# CaRe_Schematic_SMD_KRITIKARE.net
KiCad netlist of a schematic drawn in Altium Designer
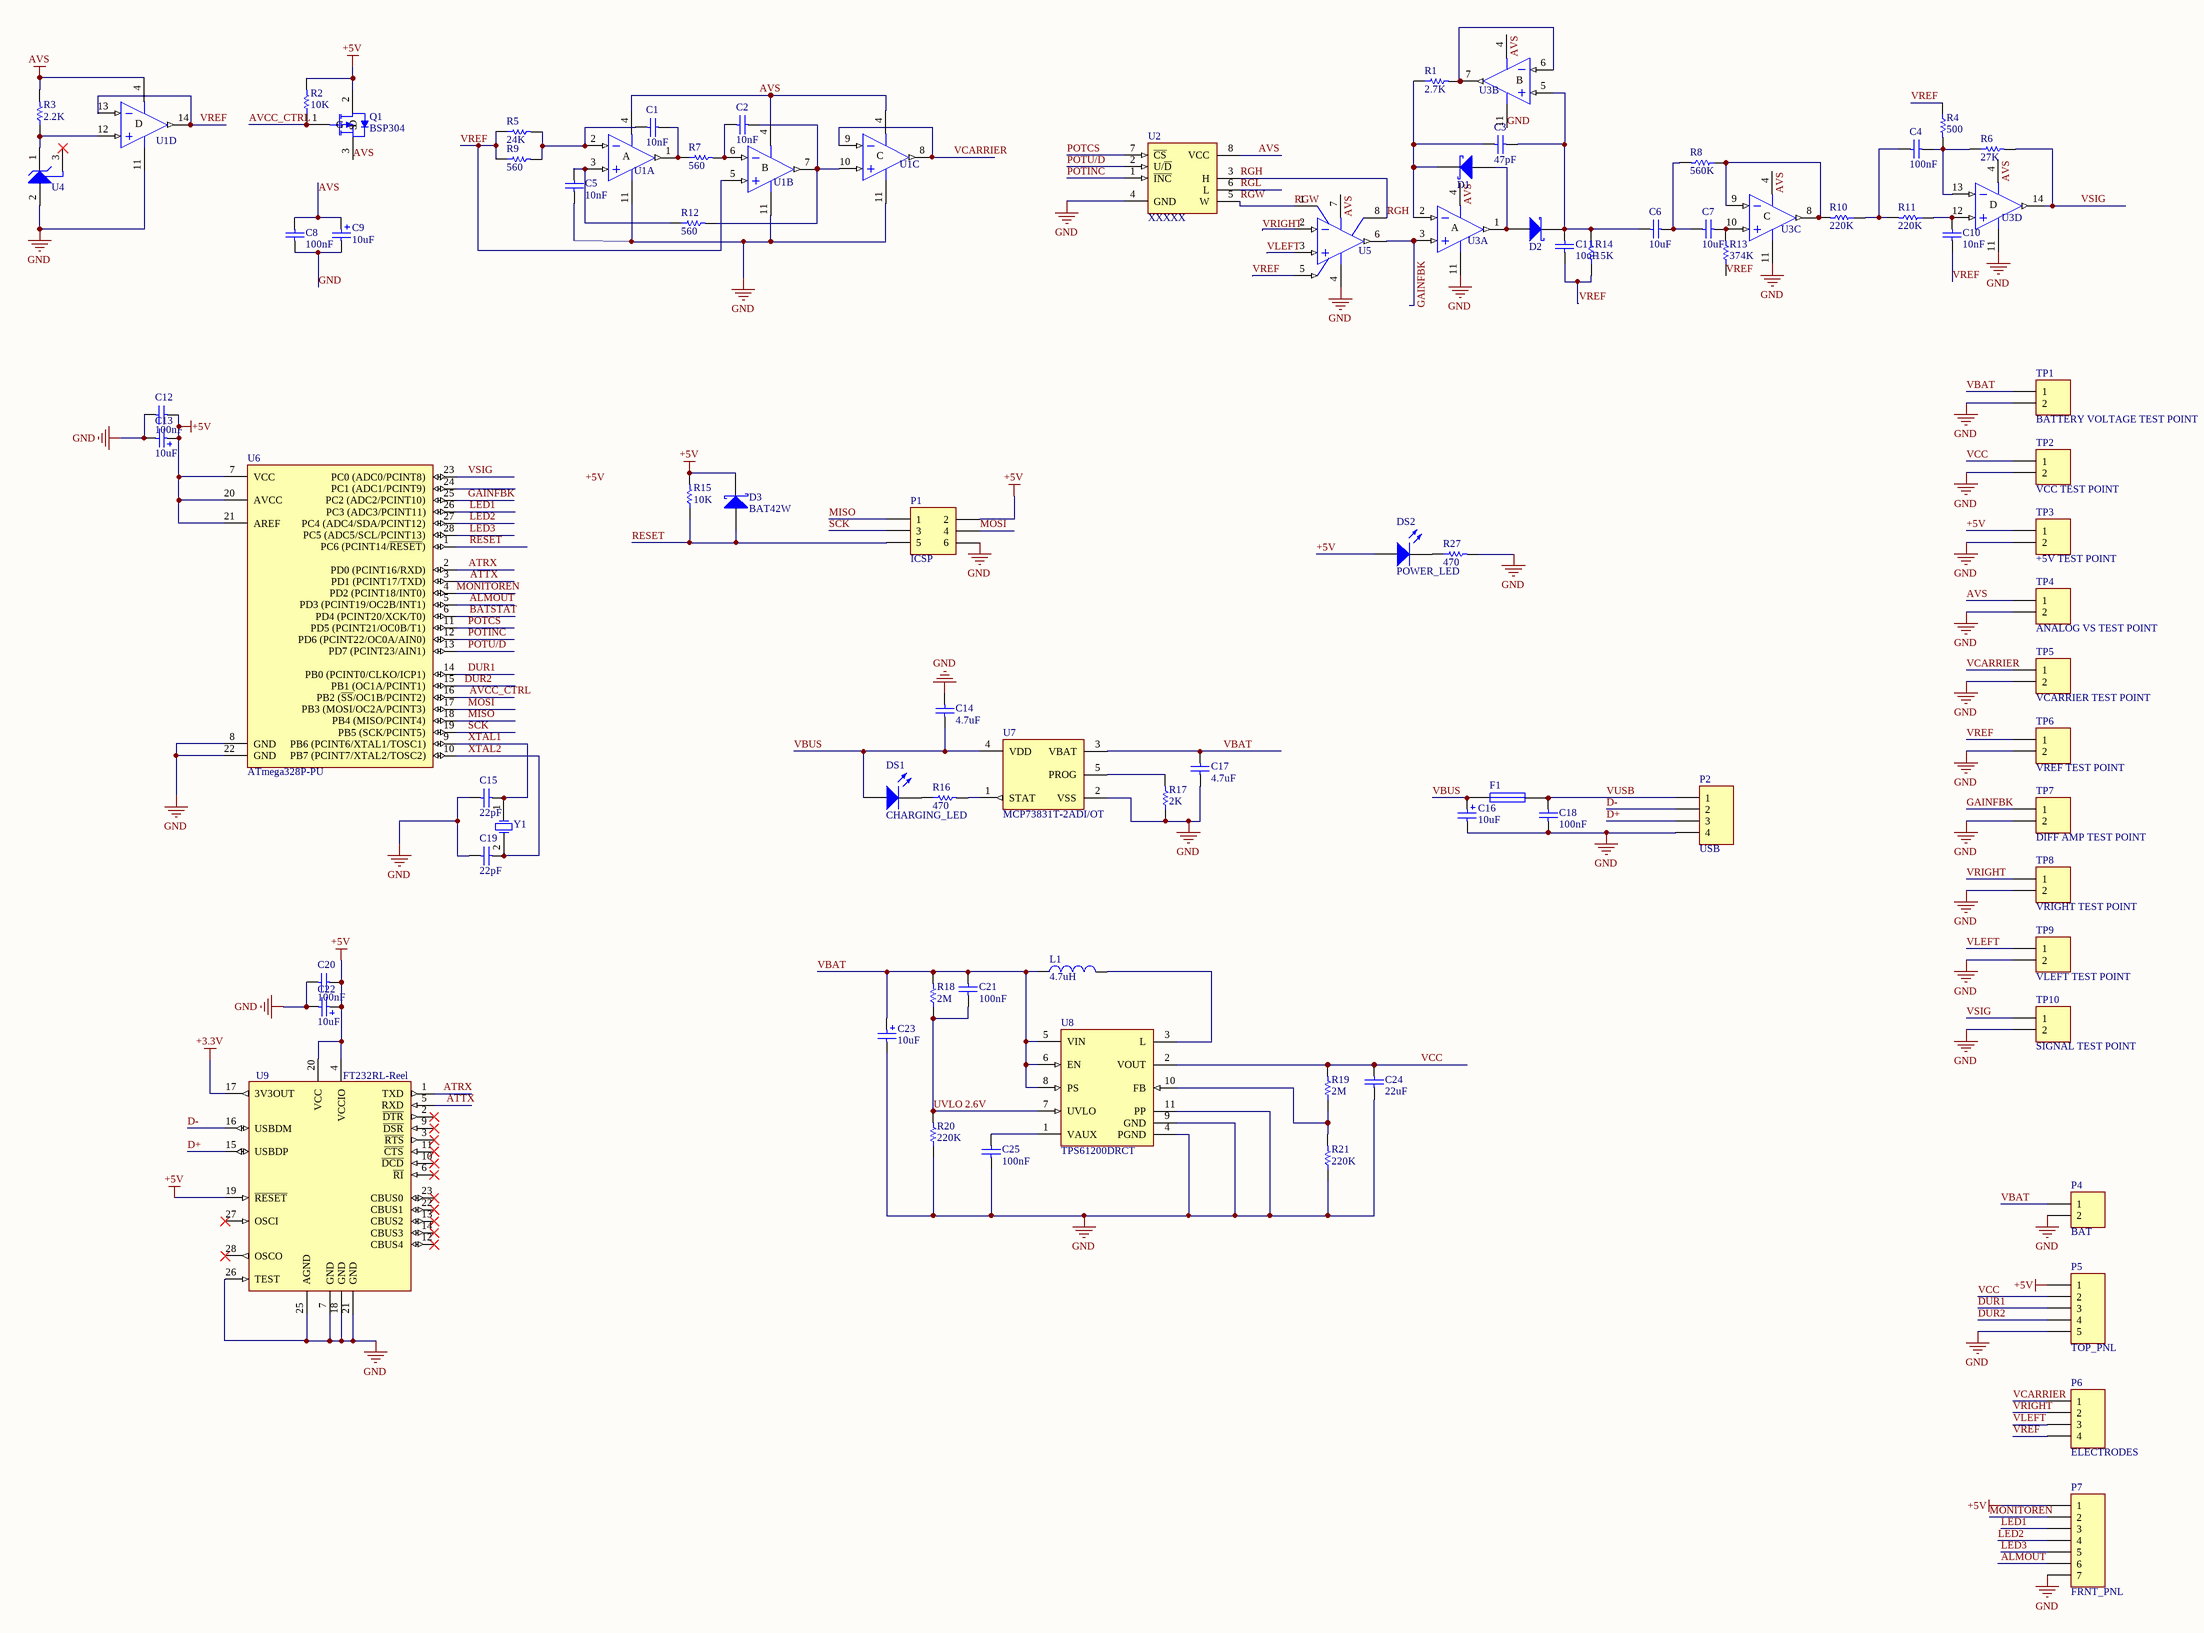
[diagram p0: CaRe_Schematic_SMD_KRITIKARE.SchDoc]

(export (version "E")
  (design (tool "Eeschema 10.0.6"))
  (components
    (comp (ref "C1")
      (value "10nF")
      (footprint "CAP0805")
      (description "Capacitor")
      (fields (field (name "PUBLISHER") "Altium Limited"))
      (libsource (lib "CaRe_SchematicLib") (part "Chip Cap"))
    )
    (comp (ref "C2")
      (value "10nF")
      (footprint "CAP0805")
      (description "Capacitor")
      (fields (field (name "PUBLISHER") "Altium Limited"))
      (libsource (lib "CaRe_SchematicLib") (part "Chip Cap"))
    )
    (comp (ref "C3")
      (value "47pF")
      (footprint "CAP0805")
      (description "Capacitor")
      (fields (field (name "PUBLISHER") "Altium Limited"))
      (libsource (lib "CaRe_SchematicLib") (part "Chip Cap"))
    )
    (comp (ref "C4")
      (value "100nF")
      (footprint "CAP0805")
      (description "Capacitor")
      (fields (field (name "PUBLISHER") "Altium Limited"))
      (libsource (lib "CaRe_SchematicLib") (part "Chip Cap"))
    )
    (comp (ref "C5")
      (value "10nF")
      (footprint "CAP0805")
      (description "Capacitor")
      (fields (field (name "PUBLISHER") "Altium Limited"))
      (libsource (lib "CaRe_SchematicLib") (part "Chip Cap"))
    )
    (comp (ref "C6")
      (value "10uF")
      (footprint "CAP0805")
      (description "Capacitor")
      (fields (field (name "PUBLISHER") "Altium Limited"))
      (libsource (lib "CaRe_SchematicLib") (part "Chip Cap"))
    )
    (comp (ref "C7")
      (value "10uF")
      (footprint "CAP0805")
      (description "Capacitor")
      (fields (field (name "PUBLISHER") "Altium Limited"))
      (libsource (lib "CaRe_SchematicLib") (part "Chip Cap"))
    )
    (comp (ref "C8")
      (value "100nF")
      (footprint "CAP0805")
      (description "Capacitor")
      (fields (field (name "PUBLISHER") "Altium Limited"))
      (libsource (lib "CaRe_SchematicLib") (part "Chip Cap"))
    )
    (comp (ref "C9")
      (value "10uF")
      (footprint "0805TANTCAP")
      (description "Polarized Capacitor (Radial)")
      (fields
        (field (name "MANUFACTURER") "AVX")
        (field (name "PART NUMBER") "TAJP106M010RNJ")
        (field (name "PUBLISHER") "Altium Limited")
      )
      (libsource (lib "CaRe_SchematicLib") (part "Cap Tant"))
    )
    (comp (ref "C10")
      (value "10nF")
      (footprint "CAP0805")
      (description "Capacitor")
      (fields (field (name "PUBLISHER") "Altium Limited"))
      (libsource (lib "CaRe_SchematicLib") (part "Chip Cap"))
    )
    (comp (ref "C11")
      (value "10uF")
      (footprint "CAP0805")
      (description "Capacitor")
      (fields (field (name "PUBLISHER") "Altium Limited"))
      (libsource (lib "CaRe_SchematicLib") (part "Chip Cap"))
    )
    (comp (ref "C12")
      (value "100nF")
      (footprint "CAP0805")
      (description "Capacitor")
      (fields (field (name "PUBLISHER") "Altium Limited"))
      (libsource (lib "CaRe_SchematicLib") (part "Chip Cap"))
    )
    (comp (ref "C13")
      (value "10uF")
      (footprint "0805TANTCAP")
      (description "Polarized Capacitor (Radial)")
      (fields
        (field (name "MANUFACTURER") "AVX")
        (field (name "PART NUMBER") "TAJP106M010RNJ")
        (field (name "PUBLISHER") "Altium Limited")
      )
      (libsource (lib "CaRe_SchematicLib") (part "Cap Tant"))
    )
    (comp (ref "C14")
      (value "4.7uF")
      (footprint "CAP0805")
      (description "Capacitor")
      (fields (field (name "PUBLISHER") "Altium Limited"))
      (libsource (lib "CaRe_SchematicLib") (part "Chip Cap"))
    )
    (comp (ref "C15")
      (value "22pF")
      (footprint "CAP0805")
      (description "Capacitor")
      (fields (field (name "PUBLISHER") "Altium Limited"))
      (libsource (lib "CaRe_SchematicLib") (part "Chip Cap"))
    )
    (comp (ref "C16")
      (value "10uF")
      (footprint "0805TANTCAP")
      (description "Polarized Capacitor (Radial)")
      (fields
        (field (name "MANUFACTURER") "AVX")
        (field (name "PART NUMBER") "TAJP106M010RNJ")
        (field (name "PUBLISHER") "Altium Limited")
      )
      (libsource (lib "CaRe_SchematicLib") (part "Cap Tant"))
    )
    (comp (ref "C17")
      (value "4.7uF")
      (footprint "CAP0805")
      (description "Capacitor")
      (fields (field (name "PUBLISHER") "Altium Limited"))
      (libsource (lib "CaRe_SchematicLib") (part "Chip Cap"))
    )
    (comp (ref "C18")
      (value "100nF")
      (footprint "CAP0805")
      (description "Capacitor")
      (fields (field (name "PUBLISHER") "Altium Limited"))
      (libsource (lib "CaRe_SchematicLib") (part "Chip Cap"))
    )
    (comp (ref "C19")
      (value "22pF")
      (footprint "CAP0805")
      (description "Capacitor")
      (fields (field (name "PUBLISHER") "Altium Limited"))
      (libsource (lib "CaRe_SchematicLib") (part "Chip Cap"))
    )
    (comp (ref "C20")
      (value "100nF")
      (footprint "CAP0805")
      (description "Capacitor")
      (fields (field (name "PUBLISHER") "Altium Limited"))
      (libsource (lib "CaRe_SchematicLib") (part "Chip Cap"))
    )
    (comp (ref "C21")
      (value "100nF")
      (footprint "CAP0805")
      (description "Capacitor")
      (fields (field (name "PUBLISHER") "Altium Limited"))
      (libsource (lib "CaRe_SchematicLib") (part "Chip Cap"))
    )
    (comp (ref "C22")
      (value "10uF")
      (footprint "0805TANTCAP")
      (description "Polarized Capacitor (Radial)")
      (fields
        (field (name "MANUFACTURER") "AVX")
        (field (name "PART NUMBER") "TAJP106M010RNJ")
        (field (name "PUBLISHER") "Altium Limited")
      )
      (libsource (lib "CaRe_SchematicLib") (part "Cap Tant"))
    )
    (comp (ref "C23")
      (value "10uF")
      (footprint "0805TANTCAP")
      (description "Polarized Capacitor (Radial)")
      (fields
        (field (name "MANUFACTURER") "AVX")
        (field (name "PART NUMBER") "TAJP106M010RNJ")
        (field (name "PUBLISHER") "Altium Limited")
      )
      (libsource (lib "CaRe_SchematicLib") (part "Cap Tant"))
    )
    (comp (ref "C24")
      (value "22uF")
      (footprint "CAP0805")
      (description "Capacitor")
      (fields (field (name "PUBLISHER") "Altium Limited"))
      (libsource (lib "CaRe_SchematicLib") (part "Chip Cap"))
    )
    (comp (ref "C25")
      (value "100nF")
      (footprint "CAP0805")
      (description "Capacitor")
      (fields (field (name "PUBLISHER") "Altium Limited"))
      (libsource (lib "CaRe_SchematicLib") (part "Chip Cap"))
    )
    (comp (ref "D1")
      (value "BAT42W")
      (footprint "SOD-523")
      (description "Schottky Diode")
      (fields (field (name "MANUFACTURER") "Vishay") (field (name "PUBLISHER") "Altium Limited"))
      (libsource (lib "CaRe_SchematicLib") (part "BAT42W"))
    )
    (comp (ref "D2")
      (value "BAT42W")
      (footprint "SOD-523")
      (description "Schottky Diode")
      (fields (field (name "MANUFACTURER") "Vishay") (field (name "PUBLISHER") "Altium Limited"))
      (libsource (lib "CaRe_SchematicLib") (part "BAT42W"))
    )
    (comp (ref "D3")
      (value "BAT42W")
      (footprint "SOD-523")
      (description "Schottky Diode")
      (fields (field (name "MANUFACTURER") "Vishay") (field (name "PUBLISHER") "Altium Limited"))
      (libsource (lib "CaRe_SchematicLib") (part "BAT42W"))
    )
    (comp (ref "DS1")
      (value "CHARGING_LED")
      (footprint "CHIP_LED0805")
      (description "Typical RED LED")
      (fields (field (name "PART NUMBER") "P_100_LTST-C170KRKT") (field (name "PUBLISHER") "Altium Limited"))
      (libsource (lib "CaRe_SchematicLib") (part "CHIPLED_RED"))
    )
    (comp (ref "DS2")
      (value "POWER_LED")
      (footprint "CHIP_LED0805")
      (description "Typical RED LED")
      (fields (field (name "PART NUMBER") "P_100_LTST-C170KRKT") (field (name "PUBLISHER") "Altium Limited"))
      (libsource (lib "CaRe_SchematicLib") (part "CHIPLED_RED"))
    )
    (comp (ref "F1")
      (value "MF-MSMF050-1")
      (footprint "MF-MSMF050 FOOTPRINT")
      (description "PTC Resettable Fuse 500 mA")
      (fields (field (name "PUBLISHER") "Altium Limited"))
      (libsource (lib "CaRe_SchematicLib") (part "PTC Fuse"))
    )
    (comp (ref "L1")
      (value "4.7uH")
      (footprint "INDP4330X10N")
      (description "Inductor")
      (fields (field (name "PUBLISHER") "Altium Limited"))
      (libsource (lib "CaReSchlib1") (part "Inductor"))
    )
    (comp (ref "P1")
      (value "ICSP")
      (footprint "HDR2X3")
      (description "Header, 3-Pin, Dual row")
      (fields (field (name "PUBLISHER") "Altium Limited"))
      (libsource (lib "Miscellaneous Connectors") (part "Header 3X2"))
    )
    (comp (ref "P2")
      (value "USB")
      (footprint "JST 4-Pin SMD")
      (description "Header, 4-Pin")
      (fields (field (name "PUBLISHER") "Altium Limited"))
      (libsource (lib "Miscellaneous Connectors") (part "Header 4"))
    )
    (comp (ref "P4")
      (value "BAT")
      (footprint "JST-2 Pin SMD Connector")
      (description "Header, 2-Pin")
      (fields (field (name "PUBLISHER") "Altium Limited"))
      (libsource (lib "Miscellaneous Connectors") (part "Header 2"))
    )
    (comp (ref "P5")
      (value "TOP_PNL")
      (footprint "JST 5 Pin SMD")
      (description "Header, 5-Pin")
      (fields (field (name "PUBLISHER") "Altium Limited"))
      (libsource (lib "CaRe_SchematicLib") (part "Header 5"))
    )
    (comp (ref "P6")
      (value "ELECTRODES")
      (footprint "JST 4-Pin SMD")
      (description "Header, 4-Pin")
      (fields (field (name "PUBLISHER") "Altium Limited"))
      (libsource (lib "Miscellaneous Connectors") (part "Header 4"))
    )
    (comp (ref "P7")
      (value "FRNT_PNL")
      (footprint "JST-SH 7-Pin Vertical SMD")
      (description "Header, 7-Pin")
      (fields (field (name "PUBLISHER") "Altium Limited"))
      (libsource (lib "CaRe_SchematicLib") (part "Header 7"))
    )
    (comp (ref "Q1")
      (value "BSP304")
      (footprint "SOT23_L")
      (description "P-channel Enhancement Mode Vertical D-MOSFET")
      (fields (field (name "PUBLISHER") "Altium Limited"))
      (libsource (lib "Philips Discrete MOSFET - Power") (part "BSP304"))
    )
    (comp (ref "R1")
      (value "2.7K")
      (footprint "RES0805")
      (description "Resistor")
      (fields (field (name "PUBLISHER") "Altium Limited"))
      (libsource (lib "CaRe_SchematicLib") (part "Chip Res"))
    )
    (comp (ref "R2")
      (value "10K")
      (footprint "RES0805")
      (description "Resistor")
      (fields (field (name "PUBLISHER") "Altium Limited"))
      (libsource (lib "CaRe_SchematicLib") (part "Chip Res"))
    )
    (comp (ref "R3")
      (value "2.2K")
      (footprint "RES0805")
      (description "Resistor")
      (fields (field (name "PUBLISHER") "Altium Limited"))
      (libsource (lib "CaRe_SchematicLib") (part "Chip Res"))
    )
    (comp (ref "R4")
      (value "500")
      (footprint "RES0805")
      (description "Resistor")
      (fields (field (name "PUBLISHER") "Altium Limited"))
      (libsource (lib "CaRe_SchematicLib") (part "Chip Res"))
    )
    (comp (ref "R5")
      (value "24K")
      (footprint "RES0805")
      (description "Resistor")
      (fields (field (name "PUBLISHER") "Altium Limited"))
      (libsource (lib "CaRe_SchematicLib") (part "Chip Res"))
    )
    (comp (ref "R6")
      (value "27K")
      (footprint "RES0805")
      (description "Resistor")
      (fields (field (name "PUBLISHER") "Altium Limited"))
      (libsource (lib "CaRe_SchematicLib") (part "Chip Res"))
    )
    (comp (ref "R7")
      (value "560")
      (footprint "RES0805")
      (description "Resistor")
      (fields (field (name "PUBLISHER") "Altium Limited"))
      (libsource (lib "CaRe_SchematicLib") (part "Chip Res"))
    )
    (comp (ref "R8")
      (value "560K")
      (footprint "RES0805")
      (description "Resistor")
      (fields (field (name "PUBLISHER") "Altium Limited"))
      (libsource (lib "CaRe_SchematicLib") (part "Chip Res"))
    )
    (comp (ref "R9")
      (value "560")
      (footprint "RES0805")
      (description "Resistor")
      (fields (field (name "PUBLISHER") "Altium Limited"))
      (libsource (lib "CaRe_SchematicLib") (part "Chip Res"))
    )
    (comp (ref "R10")
      (value "220K")
      (footprint "RES0805")
      (description "Resistor")
      (fields (field (name "PUBLISHER") "Altium Limited"))
      (libsource (lib "CaRe_SchematicLib") (part "Chip Res"))
    )
    (comp (ref "R11")
      (value "220K")
      (footprint "RES0805")
      (description "Resistor")
      (fields (field (name "PUBLISHER") "Altium Limited"))
      (libsource (lib "CaRe_SchematicLib") (part "Chip Res"))
    )
    (comp (ref "R12")
      (value "560")
      (footprint "RES0805")
      (description "Resistor")
      (fields (field (name "PUBLISHER") "Altium Limited"))
      (libsource (lib "CaRe_SchematicLib") (part "Chip Res"))
    )
    (comp (ref "R13")
      (value "374K")
      (footprint "RES0805")
      (description "Resistor")
      (fields (field (name "PUBLISHER") "Altium Limited"))
      (libsource (lib "CaRe_SchematicLib") (part "Chip Res"))
    )
    (comp (ref "R14")
      (value "15K")
      (footprint "RES0805")
      (description "Resistor")
      (fields (field (name "PUBLISHER") "Altium Limited"))
      (libsource (lib "CaRe_SchematicLib") (part "Chip Res"))
    )
    (comp (ref "R15")
      (value "10K")
      (footprint "RES0805")
      (description "Resistor")
      (fields (field (name "PUBLISHER") "Altium Limited"))
      (libsource (lib "CaRe_SchematicLib") (part "Chip Res"))
    )
    (comp (ref "R16")
      (value "470")
      (footprint "RES0805")
      (description "Resistor")
      (fields (field (name "PUBLISHER") "Altium Limited"))
      (libsource (lib "CaRe_SchematicLib") (part "Chip Res"))
    )
    (comp (ref "R17")
      (value "2K")
      (footprint "RES0805")
      (description "Resistor")
      (fields (field (name "PUBLISHER") "Altium Limited"))
      (libsource (lib "CaRe_SchematicLib") (part "Chip Res"))
    )
    (comp (ref "R18")
      (value "2M")
      (footprint "RES0805")
      (description "Resistor")
      (fields (field (name "PUBLISHER") "Altium Limited"))
      (libsource (lib "CaRe_SchematicLib") (part "Chip Res"))
    )
    (comp (ref "R19")
      (value "2M")
      (footprint "RES0805")
      (description "Resistor")
      (fields (field (name "PUBLISHER") "Altium Limited"))
      (libsource (lib "CaRe_SchematicLib") (part "Chip Res"))
    )
    (comp (ref "R20")
      (value "220K")
      (footprint "RES0805")
      (description "Resistor")
      (fields (field (name "PUBLISHER") "Altium Limited"))
      (libsource (lib "CaRe_SchematicLib") (part "Chip Res"))
    )
    (comp (ref "R21")
      (value "220K")
      (footprint "RES0805")
      (description "Resistor")
      (fields (field (name "PUBLISHER") "Altium Limited"))
      (libsource (lib "CaRe_SchematicLib") (part "Chip Res"))
    )
    (comp (ref "R27")
      (value "470")
      (footprint "RES0805")
      (description "Resistor")
      (fields (field (name "PUBLISHER") "Altium Limited"))
      (libsource (lib "CaRe_SchematicLib") (part "Chip Res"))
    )
    (comp (ref "TP1")
      (value "BATTERY VOLTAGE TEST POINT")
      (footprint "HDR1X2")
      (description "Header, 2-Pin")
      (fields (field (name "PUBLISHER") "Altium Limited"))
      (libsource (lib "CaRe_SchematicLib") (part "Header 2"))
    )
    (comp (ref "TP2")
      (value "VCC TEST POINT")
      (footprint "HDR1X2")
      (description "Header, 2-Pin")
      (fields (field (name "PUBLISHER") "Altium Limited"))
      (libsource (lib "CaRe_SchematicLib") (part "Header 2"))
    )
    (comp (ref "TP3")
      (value "+5V TEST POINT")
      (footprint "HDR1X2")
      (description "Header, 2-Pin")
      (fields (field (name "PUBLISHER") "Altium Limited"))
      (libsource (lib "CaRe_SchematicLib") (part "Header 2"))
    )
    (comp (ref "TP4")
      (value "ANALOG VS TEST POINT")
      (footprint "HDR1X2")
      (description "Header, 2-Pin")
      (fields (field (name "PUBLISHER") "Altium Limited"))
      (libsource (lib "CaRe_SchematicLib") (part "Header 2"))
    )
    (comp (ref "TP5")
      (value "VCARRIER TEST POINT")
      (footprint "HDR1X2")
      (description "Header, 2-Pin")
      (fields (field (name "PUBLISHER") "Altium Limited"))
      (libsource (lib "CaRe_SchematicLib") (part "Header 2"))
    )
    (comp (ref "TP6")
      (value "VREF TEST POINT")
      (footprint "HDR1X2")
      (description "Header, 2-Pin")
      (fields (field (name "PUBLISHER") "Altium Limited"))
      (libsource (lib "CaRe_SchematicLib") (part "Header 2"))
    )
    (comp (ref "TP7")
      (value "DIFF AMP TEST POINT")
      (footprint "HDR1X2")
      (description "Header, 2-Pin")
      (fields (field (name "PUBLISHER") "Altium Limited"))
      (libsource (lib "CaRe_SchematicLib") (part "Header 2"))
    )
    (comp (ref "TP8")
      (value "VRIGHT TEST POINT")
      (footprint "HDR1X2")
      (description "Header, 2-Pin")
      (fields (field (name "PUBLISHER") "Altium Limited"))
      (libsource (lib "CaRe_SchematicLib") (part "Header 2"))
    )
    (comp (ref "TP9")
      (value "VLEFT TEST POINT")
      (footprint "HDR1X2")
      (description "Header, 2-Pin")
      (fields (field (name "PUBLISHER") "Altium Limited"))
      (libsource (lib "CaRe_SchematicLib") (part "Header 2"))
    )
    (comp (ref "TP10")
      (value "SIGNAL TEST POINT")
      (footprint "HDR1X2")
      (description "Header, 2-Pin")
      (fields (field (name "PUBLISHER") "Altium Limited"))
      (libsource (lib "CaRe_SchematicLib") (part "Header 2"))
    )
    (comp (ref "U1")
      (value "TLV274IN")
      (footprint "TI-D14_L")
      (description "JFET-Input Operational Amplifier")
      (fields (field (name "PUBLISHER") "Altium Limited"))
      (libsource (lib "CaReSchlib1") (part "TLV274IN"))
    )
    (comp (ref "U2")
      (value "XXXXX")
      (footprint "SOIC-8")
      (description "Nonvolatile Trimmer Potentiometer")
      (fields (field (name "PUBLISHER") "Altium Limited"))
      (libsource (lib "Dallas Interface Digital Potentiometer") (part "DS1804-050"))
    )
    (comp (ref "U3")
      (value "TLV274IN")
      (footprint "TI-D14_L")
      (description "JFET-Input Operational Amplifier")
      (fields (field (name "PUBLISHER") "Altium Limited"))
      (libsource (lib "CaReSchlib1") (part "TLV274IN"))
    )
    (comp (ref "U4")
      (value "LM4040")
      (footprint "SOT23_L")
      (fields (field (name "PARTNUMBER") "LM4040A25IDBZR") (field (name "MANUFACTURER") "Texas Instruments"))
      (libsource (lib "CaRe_SchematicLib") (part "LM4040"))
    )
    (comp (ref "U5")
      (value "LT1920")
      (footprint "LT-S8-8_L(LT1920)")
      (description "Low-Cost, Low-Power Instrumentation Amplifier")
      (fields (field (name "PUBLISHER") "Altium Limited"))
      (libsource (lib "AD Instrumentation Amplifier") (part "AD620AN"))
    )
    (comp (ref "U6")
      (value "ATmega328P-PU")
      (footprint "28P3")
      (fields (field (name "PUBLISHER") "Altium Limited"))
      (libsource (lib "CaReSchlib1") (part "ATmega328P-PU"))
    )
    (comp (ref "U7")
      (value "MCP73831T-2ADI/OT")
      (footprint "SOT-23-OT5_L")
      (fields (field (name "MANUFACTURER") "Microchip"))
      (libsource (lib "CaRe_SchematicLib") (part "MCP73831T-2ADI/OT"))
    )
    (comp (ref "U8")
      (value "TPS61200DRCT")
      (footprint "DRC10-2400X1650TP")
      (fields (field (name "MANUFACTURER") "Texas Instruments"))
      (libsource (lib "CaRe_SchematicLib") (part "TPS61200DRCT"))
    )
    (comp (ref "U9")
      (value "FT232RL-Reel")
      (footprint "SSOP-28_L(FTDI)")
      (description "USB UART Asynchronous Serial Data Transfer Chip, SSOP-28, Tape and Reel")
      (fields (field (name "PUBLISHER") "Altium Limited"))
      (libsource (lib "FTDI Communication UART") (part "FT232RL-Reel"))
    )
    (comp (ref "Y1")
      (value "ECS-10-3-1")
      (footprint "HC-49U")
      (description "Crystal Oscillator")
      (fields (field (name "PUBLISHER") "Altium Limited"))
      (libsource (lib "ECS Crystal Oscillator") (part "ECS-10-13-1"))
    )
  )
  (nets
    (net (code "1") (name "+3.3V") (class "Default")
      (node (ref "U9") (pin "17") (pinfunction "3V3OUT_17") (pintype "output"))
    )
    (net (code "2") (name "+5V") (class "Default")
      (node (ref "C12") (pin "1") (pinfunction "1_1") (pintype "passive"))
      (node (ref "C13") (pin "1") (pinfunction "1_1") (pintype "passive"))
      (node (ref "C20") (pin "1") (pinfunction "1_1") (pintype "passive"))
      (node (ref "C22") (pin "1") (pinfunction "1_1") (pintype "passive"))
      (node (ref "D3") (pin "2") (pinfunction "2_2") (pintype "passive"))
      (node (ref "DS2") (pin "1") (pinfunction "A_1") (pintype "passive"))
      (node (ref "P1") (pin "2") (pinfunction "2_2") (pintype "passive"))
      (node (ref "P5") (pin "1") (pinfunction "1_1") (pintype "passive"))
      (node (ref "P7") (pin "1") (pinfunction "1_1") (pintype "passive"))
      (node (ref "Q1") (pin "2") (pinfunction "D_2") (pintype "passive"))
      (node (ref "R15") (pin "2") (pinfunction "2_2") (pintype "passive"))
      (node (ref "R2") (pin "2") (pinfunction "2_2") (pintype "passive"))
      (node (ref "TP3") (pin "1") (pinfunction "1_1") (pintype "passive"))
      (node (ref "U6") (pin "20") (pinfunction "AVCC_20") (pintype "power_in"))
      (node (ref "U6") (pin "21") (pinfunction "AREF_21") (pintype "power_in"))
      (node (ref "U6") (pin "7") (pinfunction "VCC_7") (pintype "power_in"))
      (node (ref "U9") (pin "19") (pinfunction "~{RESET}_19") (pintype "input"))
      (node (ref "U9") (pin "20") (pinfunction "VCC_20") (pintype "power_in"))
      (node (ref "U9") (pin "4") (pinfunction "VCCIO_4") (pintype "power_in"))
    )
    (net (code "3") (name "/ALMOUT") (class "Default")
      (node (ref "P7") (pin "6") (pinfunction "6_6") (pintype "passive"))
      (node (ref "U6") (pin "5") (pinfunction "PD3_(PCINT19/OC2B/INT1)_5") (pintype "bidirectional"))
    )
    (net (code "4") (name "/ATRX") (class "Default")
      (node (ref "U6") (pin "2") (pinfunction "PD0_(PCINT16/RXD)_2") (pintype "bidirectional"))
      (node (ref "U9") (pin "1") (pinfunction "TXD_1") (pintype "output"))
    )
    (net (code "5") (name "/ATTX") (class "Default")
      (node (ref "U6") (pin "3") (pinfunction "PD1_(PCINT17/TXD)_3") (pintype "bidirectional"))
      (node (ref "U9") (pin "5") (pinfunction "RXD_5") (pintype "input"))
    )
    (net (code "6") (name "/AVCC_CTRL") (class "Default")
      (node (ref "Q1") (pin "1") (pinfunction "G_1") (pintype "passive"))
      (node (ref "R2") (pin "1") (pinfunction "1_1") (pintype "passive"))
      (node (ref "U6") (pin "16") (pinfunction "PB2_(~{SS}/OC1B/PCINT2)_16") (pintype "bidirectional"))
    )
    (net (code "7") (name "/BATSTAT") (class "Default")
      (node (ref "U6") (pin "6") (pinfunction "PD4_(PCINT20/XCK/T0)_6") (pintype "bidirectional"))
    )
    (net (code "8") (name "/D+") (class "Default")
      (node (ref "P2") (pin "3") (pinfunction "3_3") (pintype "passive"))
      (node (ref "U9") (pin "15") (pinfunction "USBDP_15") (pintype "bidirectional"))
    )
    (net (code "9") (name "/D-") (class "Default")
      (node (ref "P2") (pin "2") (pinfunction "2_2") (pintype "passive"))
      (node (ref "U9") (pin "16") (pinfunction "USBDM_16") (pintype "bidirectional"))
    )
    (net (code "10") (name "/DUR1") (class "Default")
      (node (ref "P5") (pin "3") (pinfunction "3_3") (pintype "passive"))
      (node (ref "U6") (pin "14") (pinfunction "PB0_(PCINT0/CLKO/ICP1)_14") (pintype "bidirectional"))
    )
    (net (code "11") (name "/DUR2") (class "Default")
      (node (ref "P5") (pin "4") (pinfunction "4_4") (pintype "passive"))
      (node (ref "U6") (pin "15") (pinfunction "PB1_(OC1A/PCINT1)_15") (pintype "bidirectional"))
    )
    (net (code "12") (name "/GAINFBK") (class "Default")
      (node (ref "TP7") (pin "1") (pinfunction "1_1") (pintype "passive"))
      (node (ref "U3") (pin "3") (pinfunction "IN+_3") (pintype "input"))
      (node (ref "U5") (pin "6") (pinfunction "OUT_6") (pintype "output"))
      (node (ref "U6") (pin "25") (pinfunction "PC2_(ADC2/PCINT10)_25") (pintype "bidirectional"))
    )
    (net (code "13") (name "/LED1") (class "Default")
      (node (ref "P7") (pin "3") (pinfunction "3_3") (pintype "passive"))
      (node (ref "U6") (pin "26") (pinfunction "PC3_(ADC3/PCINT11)_26") (pintype "bidirectional"))
    )
    (net (code "14") (name "/LED2") (class "Default")
      (node (ref "P7") (pin "4") (pinfunction "4_4") (pintype "passive"))
      (node (ref "U6") (pin "27") (pinfunction "PC4_(ADC4/SDA/PCINT12)_27") (pintype "bidirectional"))
    )
    (net (code "15") (name "/LED3") (class "Default")
      (node (ref "P7") (pin "5") (pinfunction "5_5") (pintype "passive"))
      (node (ref "U6") (pin "28") (pinfunction "PC5_(ADC5/SCL/PCINT13)_28") (pintype "bidirectional"))
    )
    (net (code "16") (name "/MISO") (class "Default")
      (node (ref "P1") (pin "1") (pinfunction "1_1") (pintype "passive"))
      (node (ref "U6") (pin "18") (pinfunction "PB4_(MISO/PCINT4)_18") (pintype "bidirectional"))
    )
    (net (code "17") (name "/MONITOREN") (class "Default")
      (node (ref "P7") (pin "2") (pinfunction "2_2") (pintype "passive"))
      (node (ref "U6") (pin "4") (pinfunction "PD2_(PCINT18/INT0)_4") (pintype "bidirectional"))
    )
    (net (code "18") (name "/MOSI") (class "Default")
      (node (ref "P1") (pin "4") (pinfunction "4_4") (pintype "passive"))
      (node (ref "U6") (pin "17") (pinfunction "PB3_(MOSI/OC2A/PCINT3)_17") (pintype "bidirectional"))
    )
    (net (code "19") (name "/POTCS") (class "Default")
      (node (ref "U2") (pin "7") (pinfunction "~{CS}_7") (pintype "input"))
      (node (ref "U6") (pin "11") (pinfunction "PD5_(PCINT21/OC0B/T1)_11") (pintype "bidirectional"))
    )
    (net (code "20") (name "/POTINC") (class "Default")
      (node (ref "U2") (pin "1") (pinfunction "~{INC}_1") (pintype "input"))
      (node (ref "U6") (pin "12") (pinfunction "PD6_(PCINT22/OC0A/AIN0)_12") (pintype "bidirectional"))
    )
    (net (code "21") (name "/POTU{slash}D") (class "Default")
      (node (ref "U2") (pin "2") (pinfunction "U/~{D}_2") (pintype "input"))
      (node (ref "U6") (pin "13") (pinfunction "PD7_(PCINT23/AIN1)_13") (pintype "bidirectional"))
    )
    (net (code "22") (name "/RESET") (class "Default")
      (node (ref "D3") (pin "1") (pinfunction "1_1") (pintype "passive"))
      (node (ref "P1") (pin "5") (pinfunction "5_5") (pintype "passive"))
      (node (ref "R15") (pin "1") (pinfunction "1_1") (pintype "passive"))
      (node (ref "U6") (pin "1") (pinfunction "PC6_(PCINT14/~{RESET})_1") (pintype "bidirectional"))
    )
    (net (code "23") (name "/RGH") (class "Default")
      (node (ref "U2") (pin "3") (pinfunction "H_3") (pintype "passive"))
      (node (ref "U5") (pin "8") (pinfunction "RG_8") (pintype "passive"))
    )
    (net (code "24") (name "/RGL") (class "Default")
      (node (ref "U2") (pin "6") (pinfunction "L_6") (pintype "passive"))
    )
    (net (code "25") (name "/RGW") (class "Default")
      (node (ref "U2") (pin "5") (pinfunction "W_5") (pintype "passive"))
      (node (ref "U5") (pin "1") (pinfunction "RG_1") (pintype "passive"))
    )
    (net (code "26") (name "/SCK") (class "Default")
      (node (ref "P1") (pin "3") (pinfunction "3_3") (pintype "passive"))
      (node (ref "U6") (pin "19") (pinfunction "PB5_(SCK/PCINT5)_19") (pintype "bidirectional"))
    )
    (net (code "27") (name "/UVLO 2.6V") (class "Default")
      (node (ref "C21") (pin "1") (pinfunction "1_1") (pintype "passive"))
      (node (ref "R18") (pin "1") (pinfunction "1_1") (pintype "passive"))
      (node (ref "R20") (pin "2") (pinfunction "2_2") (pintype "passive"))
      (node (ref "U8") (pin "7") (pinfunction "UVLO_7") (pintype "input"))
    )
    (net (code "28") (name "/VBAT") (class "Default")
      (node (ref "C17") (pin "2") (pinfunction "2_2") (pintype "passive"))
      (node (ref "C21") (pin "2") (pinfunction "2_2") (pintype "passive"))
      (node (ref "C23") (pin "1") (pinfunction "1_1") (pintype "passive"))
      (node (ref "L1") (pin "1") (pinfunction "1_1") (pintype "passive"))
      (node (ref "P4") (pin "1") (pinfunction "1_1") (pintype "passive"))
      (node (ref "R18") (pin "2") (pinfunction "2_2") (pintype "passive"))
      (node (ref "TP1") (pin "1") (pinfunction "1_1") (pintype "passive"))
      (node (ref "U7") (pin "3") (pinfunction "VBAT_3") (pintype "power_in"))
      (node (ref "U8") (pin "5") (pinfunction "VIN_5") (pintype "power_in"))
      (node (ref "U8") (pin "6") (pinfunction "EN_6") (pintype "input"))
      (node (ref "U8") (pin "8") (pinfunction "PS_8") (pintype "input"))
    )
    (net (code "29") (name "/VBUS") (class "Default")
      (node (ref "C14") (pin "2") (pinfunction "2_2") (pintype "passive"))
      (node (ref "C16") (pin "1") (pinfunction "1_1") (pintype "passive"))
      (node (ref "DS1") (pin "1") (pinfunction "A_1") (pintype "passive"))
      (node (ref "F1") (pin "2") (pinfunction "2_2") (pintype "passive"))
      (node (ref "U7") (pin "4") (pinfunction "VDD_4") (pintype "power_in"))
    )
    (net (code "30") (name "/VCARRIER") (class "Default")
      (node (ref "P6") (pin "1") (pinfunction "1_1") (pintype "passive"))
      (node (ref "TP5") (pin "1") (pinfunction "1_1") (pintype "passive"))
      (node (ref "U1") (pin "8") (pinfunction "OUT_8") (pintype "output"))
      (node (ref "U1") (pin "9") (pinfunction "IN-_9") (pintype "input"))
    )
    (net (code "31") (name "/VCC") (class "Default")
      (node (ref "C24") (pin "1") (pinfunction "1_1") (pintype "passive"))
      (node (ref "P5") (pin "2") (pinfunction "2_2") (pintype "passive"))
      (node (ref "R19") (pin "2") (pinfunction "2_2") (pintype "passive"))
      (node (ref "TP2") (pin "1") (pinfunction "1_1") (pintype "passive"))
      (node (ref "U8") (pin "2") (pinfunction "VOUT_2") (pintype "power_in"))
    )
    (net (code "32") (name "/VLEFT") (class "Default")
      (node (ref "P6") (pin "3") (pinfunction "3_3") (pintype "passive"))
      (node (ref "TP9") (pin "1") (pinfunction "1_1") (pintype "passive"))
      (node (ref "U5") (pin "3") (pinfunction "+IN_3") (pintype "input"))
    )
    (net (code "33") (name "/VREF") (class "Default")
      (node (ref "C10") (pin "1") (pinfunction "1_1") (pintype "passive"))
      (node (ref "C11") (pin "1") (pinfunction "1_1") (pintype "passive"))
      (node (ref "P6") (pin "4") (pinfunction "4_4") (pintype "passive"))
      (node (ref "R13") (pin "1") (pinfunction "1_1") (pintype "passive"))
      (node (ref "R14") (pin "1") (pinfunction "1_1") (pintype "passive"))
      (node (ref "R4") (pin "1") (pinfunction "1_1") (pintype "passive"))
      (node (ref "R5") (pin "1") (pinfunction "1_1") (pintype "passive"))
      (node (ref "R9") (pin "1") (pinfunction "1_1") (pintype "passive"))
      (node (ref "TP6") (pin "1") (pinfunction "1_1") (pintype "passive"))
      (node (ref "U1") (pin "13") (pinfunction "IN-_13") (pintype "input"))
      (node (ref "U1") (pin "14") (pinfunction "OUT_14") (pintype "output"))
      (node (ref "U1") (pin "5") (pinfunction "IN+_5") (pintype "input"))
      (node (ref "U5") (pin "5") (pinfunction "REF_5") (pintype "input"))
    )
    (net (code "34") (name "/VRIGHT") (class "Default")
      (node (ref "P6") (pin "2") (pinfunction "2_2") (pintype "passive"))
      (node (ref "TP8") (pin "1") (pinfunction "1_1") (pintype "passive"))
      (node (ref "U5") (pin "2") (pinfunction "-IN_2") (pintype "input"))
    )
    (net (code "35") (name "/VSIG") (class "Default")
      (node (ref "R6") (pin "2") (pinfunction "2_2") (pintype "passive"))
      (node (ref "TP10") (pin "1") (pinfunction "1_1") (pintype "passive"))
      (node (ref "U3") (pin "14") (pinfunction "OUT_14") (pintype "output"))
      (node (ref "U6") (pin "23") (pinfunction "PC0_(ADC0/PCINT8)_23") (pintype "bidirectional"))
    )
    (net (code "36") (name "/VUSB") (class "Default")
      (node (ref "C18") (pin "2") (pinfunction "2_2") (pintype "passive"))
      (node (ref "F1") (pin "1") (pinfunction "1_1") (pintype "passive"))
      (node (ref "P2") (pin "1") (pinfunction "1_1") (pintype "passive"))
    )
    (net (code "37") (name "/XTAL1") (class "Default")
      (node (ref "C15") (pin "2") (pinfunction "2_2") (pintype "passive"))
      (node (ref "U6") (pin "9") (pinfunction "PB6_(PCINT6/XTAL1/TOSC1)_9") (pintype "bidirectional"))
      (node (ref "Y1") (pin "1") (pinfunction "OSC1_1") (pintype "passive"))
    )
    (net (code "38") (name "/XTAL2") (class "Default")
      (node (ref "C19") (pin "2") (pinfunction "2_2") (pintype "passive"))
      (node (ref "U6") (pin "10") (pinfunction "PB7_(PCINT7/XTAL2/TOSC2)_10") (pintype "bidirectional"))
      (node (ref "Y1") (pin "2") (pinfunction "OSC2_2") (pintype "passive"))
    )
    (net (code "39") (name "AVS") (class "Default")
      (node (ref "C8") (pin "2") (pinfunction "2_2") (pintype "passive"))
      (node (ref "C9") (pin "1") (pinfunction "1_1") (pintype "passive"))
      (node (ref "Q1") (pin "3") (pinfunction "S_3") (pintype "passive"))
      (node (ref "R3") (pin "2") (pinfunction "2_2") (pintype "passive"))
      (node (ref "TP4") (pin "1") (pinfunction "1_1") (pintype "passive"))
      (node (ref "U1") (pin "4") (pinfunction "V+_4") (pintype "power_in"))
      (node (ref "U2") (pin "8") (pinfunction "VCC_8") (pintype "power_in"))
      (node (ref "U3") (pin "4") (pinfunction "V+_4") (pintype "power_in"))
      (node (ref "U5") (pin "7") (pinfunction "V+_7") (pintype "power_in"))
    )
    (net (code "40") (name "GND") (class "Default")
      (node (ref "C12") (pin "2") (pinfunction "2_2") (pintype "passive"))
      (node (ref "C13") (pin "2") (pinfunction "2_2") (pintype "passive"))
      (node (ref "C14") (pin "1") (pinfunction "1_1") (pintype "passive"))
      (node (ref "C15") (pin "1") (pinfunction "1_1") (pintype "passive"))
      (node (ref "C16") (pin "2") (pinfunction "2_2") (pintype "passive"))
      (node (ref "C17") (pin "1") (pinfunction "1_1") (pintype "passive"))
      (node (ref "C18") (pin "1") (pinfunction "1_1") (pintype "passive"))
      (node (ref "C19") (pin "1") (pinfunction "1_1") (pintype "passive"))
      (node (ref "C20") (pin "2") (pinfunction "2_2") (pintype "passive"))
      (node (ref "C22") (pin "2") (pinfunction "2_2") (pintype "passive"))
      (node (ref "C23") (pin "2") (pinfunction "2_2") (pintype "passive"))
      (node (ref "C24") (pin "2") (pinfunction "2_2") (pintype "passive"))
      (node (ref "C25") (pin "1") (pinfunction "1_1") (pintype "passive"))
      (node (ref "C5") (pin "1") (pinfunction "1_1") (pintype "passive"))
      (node (ref "C8") (pin "1") (pinfunction "1_1") (pintype "passive"))
      (node (ref "C9") (pin "2") (pinfunction "2_2") (pintype "passive"))
      (node (ref "P1") (pin "6") (pinfunction "6_6") (pintype "passive"))
      (node (ref "P2") (pin "4") (pinfunction "4_4") (pintype "passive"))
      (node (ref "P4") (pin "2") (pinfunction "2_2") (pintype "passive"))
      (node (ref "P5") (pin "5") (pinfunction "5_5") (pintype "passive"))
      (node (ref "P7") (pin "7") (pinfunction "7_7") (pintype "passive"))
      (node (ref "R17") (pin "1") (pinfunction "1_1") (pintype "passive"))
      (node (ref "R20") (pin "1") (pinfunction "1_1") (pintype "passive"))
      (node (ref "R21") (pin "1") (pinfunction "1_1") (pintype "passive"))
      (node (ref "R27") (pin "2") (pinfunction "2_2") (pintype "passive"))
      (node (ref "TP1") (pin "2") (pinfunction "2_2") (pintype "passive"))
      (node (ref "TP10") (pin "2") (pinfunction "2_2") (pintype "passive"))
      (node (ref "TP2") (pin "2") (pinfunction "2_2") (pintype "passive"))
      (node (ref "TP3") (pin "2") (pinfunction "2_2") (pintype "passive"))
      (node (ref "TP4") (pin "2") (pinfunction "2_2") (pintype "passive"))
      (node (ref "TP5") (pin "2") (pinfunction "2_2") (pintype "passive"))
      (node (ref "TP6") (pin "2") (pinfunction "2_2") (pintype "passive"))
      (node (ref "TP7") (pin "2") (pinfunction "2_2") (pintype "passive"))
      (node (ref "TP8") (pin "2") (pinfunction "2_2") (pintype "passive"))
      (node (ref "TP9") (pin "2") (pinfunction "2_2") (pintype "passive"))
      (node (ref "U1") (pin "11") (pinfunction "V-_11") (pintype "power_in"))
      (node (ref "U2") (pin "4") (pinfunction "GND_4") (pintype "power_in"))
      (node (ref "U3") (pin "11") (pinfunction "V-_11") (pintype "power_in"))
      (node (ref "U4") (pin "2") (pinfunction "ANODE_2") (pintype "passive"))
      (node (ref "U5") (pin "4") (pinfunction "V-_4") (pintype "power_in"))
      (node (ref "U6") (pin "22") (pinfunction "GND_22") (pintype "power_in"))
      (node (ref "U6") (pin "8") (pinfunction "GND_8") (pintype "power_in"))
      (node (ref "U7") (pin "2") (pinfunction "VSS_2") (pintype "power_in"))
      (node (ref "U8") (pin "11") (pinfunction "PP_11") (pintype "power_in"))
      (node (ref "U8") (pin "4") (pinfunction "PGND_4") (pintype "power_in"))
      (node (ref "U8") (pin "9") (pinfunction "GND_9") (pintype "power_in"))
      (node (ref "U9") (pin "18") (pinfunction "GND_18") (pintype "power_in"))
      (node (ref "U9") (pin "21") (pinfunction "GND_21") (pintype "power_in"))
      (node (ref "U9") (pin "25") (pinfunction "AGND_25") (pintype "power_in"))
      (node (ref "U9") (pin "26") (pinfunction "TEST_26") (pintype "input"))
      (node (ref "U9") (pin "7") (pinfunction "GND_7") (pintype "power_in"))
    )
    (net (code "41") (name "Net-(C4-Pad1)") (class "Default")
      (node (ref "C4") (pin "1") (pinfunction "1_1") (pintype "passive"))
      (node (ref "R10") (pin "1") (pinfunction "1_1") (pintype "passive"))
      (node (ref "R11") (pin "2") (pinfunction "2_2") (pintype "passive"))
    )
    (net (code "42") (name "Net-(C6-Pad1)") (class "Default")
      (node (ref "C6") (pin "1") (pinfunction "1_1") (pintype "passive"))
      (node (ref "C7") (pin "2") (pinfunction "2_2") (pintype "passive"))
      (node (ref "R8") (pin "2") (pinfunction "2_2") (pintype "passive"))
    )
    (net (code "43") (name "Net-(DS1-K)") (class "Default")
      (node (ref "DS1") (pin "2") (pinfunction "K_2") (pintype "passive"))
      (node (ref "R16") (pin "1") (pinfunction "1_1") (pintype "passive"))
    )
    (net (code "44") (name "Net-(DS2-K)") (class "Default")
      (node (ref "DS2") (pin "2") (pinfunction "K_2") (pintype "passive"))
      (node (ref "R27") (pin "1") (pinfunction "1_1") (pintype "passive"))
    )
    (net (code "45") (name "Net-(U1A-IN+)") (class "Default")
      (node (ref "C5") (pin "2") (pinfunction "2_2") (pintype "passive"))
      (node (ref "R12") (pin "1") (pinfunction "1_1") (pintype "passive"))
      (node (ref "U1") (pin "3") (pinfunction "IN+_3") (pintype "input"))
    )
    (net (code "46") (name "Net-(U1A-IN-)") (class "Default")
      (node (ref "C1") (pin "1") (pinfunction "1_1") (pintype "passive"))
      (node (ref "R5") (pin "2") (pinfunction "2_2") (pintype "passive"))
      (node (ref "R9") (pin "2") (pinfunction "2_2") (pintype "passive"))
      (node (ref "U1") (pin "2") (pinfunction "IN-_2") (pintype "input"))
    )
    (net (code "47") (name "Net-(U1A-OUT)") (class "Default")
      (node (ref "C1") (pin "2") (pinfunction "2_2") (pintype "passive"))
      (node (ref "R7") (pin "1") (pinfunction "1_1") (pintype "passive"))
      (node (ref "U1") (pin "1") (pinfunction "OUT_1") (pintype "output"))
    )
    (net (code "48") (name "Net-(U1B-IN-)") (class "Default")
      (node (ref "C2") (pin "1") (pinfunction "1_1") (pintype "passive"))
      (node (ref "R7") (pin "2") (pinfunction "2_2") (pintype "passive"))
      (node (ref "U1") (pin "6") (pinfunction "IN-_6") (pintype "input"))
    )
    (net (code "49") (name "Net-(U1B-OUT)") (class "Default")
      (node (ref "C2") (pin "2") (pinfunction "2_2") (pintype "passive"))
      (node (ref "R12") (pin "2") (pinfunction "2_2") (pintype "passive"))
      (node (ref "U1") (pin "10") (pinfunction "IN+_10") (pintype "input"))
      (node (ref "U1") (pin "7") (pinfunction "OUT_7") (pintype "output"))
    )
    (net (code "50") (name "Net-(U1D-IN+)") (class "Default")
      (node (ref "R3") (pin "1") (pinfunction "1_1") (pintype "passive"))
      (node (ref "U1") (pin "12") (pinfunction "IN+_12") (pintype "input"))
      (node (ref "U4") (pin "1") (pinfunction "CATHODE_1") (pintype "passive"))
    )
    (net (code "51") (name "Net-(U3A-IN-)") (class "Default")
      (node (ref "C3") (pin "2") (pinfunction "2_2") (pintype "passive"))
      (node (ref "D1") (pin "2") (pinfunction "2_2") (pintype "passive"))
      (node (ref "R1") (pin "1") (pinfunction "1_1") (pintype "passive"))
      (node (ref "U3") (pin "2") (pinfunction "IN-_2") (pintype "input"))
    )
    (net (code "52") (name "Net-(U3A-OUT)") (class "Default")
      (node (ref "D1") (pin "1") (pinfunction "1_1") (pintype "passive"))
      (node (ref "D2") (pin "1") (pinfunction "1_1") (pintype "passive"))
      (node (ref "U3") (pin "1") (pinfunction "OUT_1") (pintype "output"))
    )
    (net (code "53") (name "Net-(U3B-IN+)") (class "Default")
      (node (ref "C11") (pin "2") (pinfunction "2_2") (pintype "passive"))
      (node (ref "C3") (pin "1") (pinfunction "1_1") (pintype "passive"))
      (node (ref "C6") (pin "2") (pinfunction "2_2") (pintype "passive"))
      (node (ref "D2") (pin "2") (pinfunction "2_2") (pintype "passive"))
      (node (ref "R14") (pin "2") (pinfunction "2_2") (pintype "passive"))
      (node (ref "U3") (pin "5") (pinfunction "IN+_5") (pintype "input"))
    )
    (net (code "54") (name "Net-(U3B-IN-)") (class "Default")
      (node (ref "R1") (pin "2") (pinfunction "2_2") (pintype "passive"))
      (node (ref "U3") (pin "6") (pinfunction "IN-_6") (pintype "input"))
      (node (ref "U3") (pin "7") (pinfunction "OUT_7") (pintype "output"))
    )
    (net (code "55") (name "Net-(U3C-IN+)") (class "Default")
      (node (ref "C7") (pin "1") (pinfunction "1_1") (pintype "passive"))
      (node (ref "R13") (pin "2") (pinfunction "2_2") (pintype "passive"))
      (node (ref "U3") (pin "10") (pinfunction "IN+_10") (pintype "input"))
    )
    (net (code "56") (name "Net-(U3C-IN-)") (class "Default")
      (node (ref "R10") (pin "2") (pinfunction "2_2") (pintype "passive"))
      (node (ref "R8") (pin "1") (pinfunction "1_1") (pintype "passive"))
      (node (ref "U3") (pin "8") (pinfunction "OUT_8") (pintype "output"))
      (node (ref "U3") (pin "9") (pinfunction "IN-_9") (pintype "input"))
    )
    (net (code "57") (name "Net-(U3D-IN+)") (class "Default")
      (node (ref "C10") (pin "2") (pinfunction "2_2") (pintype "passive"))
      (node (ref "R11") (pin "1") (pinfunction "1_1") (pintype "passive"))
      (node (ref "U3") (pin "12") (pinfunction "IN+_12") (pintype "input"))
    )
    (net (code "58") (name "Net-(U3D-IN-)") (class "Default")
      (node (ref "C4") (pin "2") (pinfunction "2_2") (pintype "passive"))
      (node (ref "R4") (pin "2") (pinfunction "2_2") (pintype "passive"))
      (node (ref "R6") (pin "1") (pinfunction "1_1") (pintype "passive"))
      (node (ref "U3") (pin "13") (pinfunction "IN-_13") (pintype "input"))
    )
    (net (code "59") (name "Net-(U7-PROG)") (class "Default")
      (node (ref "R17") (pin "2") (pinfunction "2_2") (pintype "passive"))
      (node (ref "U7") (pin "5") (pinfunction "PROG_5") (pintype "passive"))
    )
    (net (code "60") (name "Net-(U7-STAT)") (class "Default")
      (node (ref "R16") (pin "2") (pinfunction "2_2") (pintype "passive"))
      (node (ref "U7") (pin "1") (pinfunction "STAT_1") (pintype "output"))
    )
    (net (code "61") (name "Net-(U8-FB)") (class "Default")
      (node (ref "R19") (pin "1") (pinfunction "1_1") (pintype "passive"))
      (node (ref "R21") (pin "2") (pinfunction "2_2") (pintype "passive"))
      (node (ref "U8") (pin "10") (pinfunction "FB_10") (pintype "input"))
    )
    (net (code "62") (name "Net-(U8-L)") (class "Default")
      (node (ref "L1") (pin "2") (pinfunction "2_2") (pintype "passive"))
      (node (ref "U8") (pin "3") (pinfunction "L_3") (pintype "power_in"))
    )
    (net (code "63") (name "Net-(U8-VAUX)") (class "Default")
      (node (ref "C25") (pin "2") (pinfunction "2_2") (pintype "passive"))
      (node (ref "U8") (pin "1") (pinfunction "VAUX_1") (pintype "power_in"))
    )
    (net (code "64") (name "unconnected-(U4-NC-Pad3)") (class "Default")
      (node (ref "U4") (pin "3") (pinfunction "NC_3") (pintype "passive+no_connect"))
    )
    (net (code "65") (name "unconnected-(U6-PC1_(ADC1{slash}PCINT9)-Pad24)") (class "Default")
      (node (ref "U6") (pin "24") (pinfunction "PC1_(ADC1/PCINT9)_24") (pintype "bidirectional"))
    )
    (net (code "66") (name "unconnected-(U9-CBUS0-Pad23)") (class "Default")
      (node (ref "U9") (pin "23") (pinfunction "CBUS0_23") (pintype "bidirectional+no_connect"))
    )
    (net (code "67") (name "unconnected-(U9-CBUS1-Pad22)") (class "Default")
      (node (ref "U9") (pin "22") (pinfunction "CBUS1_22") (pintype "bidirectional+no_connect"))
    )
    (net (code "68") (name "unconnected-(U9-CBUS2-Pad13)") (class "Default")
      (node (ref "U9") (pin "13") (pinfunction "CBUS2_13") (pintype "bidirectional+no_connect"))
    )
    (net (code "69") (name "unconnected-(U9-CBUS3-Pad14)") (class "Default")
      (node (ref "U9") (pin "14") (pinfunction "CBUS3_14") (pintype "bidirectional+no_connect"))
    )
    (net (code "70") (name "unconnected-(U9-CBUS4-Pad12)") (class "Default")
      (node (ref "U9") (pin "12") (pinfunction "CBUS4_12") (pintype "bidirectional+no_connect"))
    )
    (net (code "71") (name "unconnected-(U9-NC-Pad8)") (class "Default")
      (node (ref "U9") (pin "8") (pinfunction "NC_8") (pintype "passive"))
    )
    (net (code "72") (name "unconnected-(U9-NC-Pad24)") (class "Default")
      (node (ref "U9") (pin "24") (pinfunction "NC_24") (pintype "passive"))
    )
    (net (code "73") (name "unconnected-(U9-OSCI-Pad27)") (class "Default")
      (node (ref "U9") (pin "27") (pinfunction "OSCI_27") (pintype "input+no_connect"))
    )
    (net (code "74") (name "unconnected-(U9-OSCO-Pad28)") (class "Default")
      (node (ref "U9") (pin "28") (pinfunction "OSCO_28") (pintype "output+no_connect"))
    )
    (net (code "75") (name "unconnected-(U9-~{CTS}-Pad11)") (class "Default")
      (node (ref "U9") (pin "11") (pinfunction "~{CTS}_11") (pintype "input+no_connect"))
    )
    (net (code "76") (name "unconnected-(U9-~{DCD}-Pad10)") (class "Default")
      (node (ref "U9") (pin "10") (pinfunction "~{DCD}_10") (pintype "input+no_connect"))
    )
    (net (code "77") (name "unconnected-(U9-~{DSR}-Pad9)") (class "Default")
      (node (ref "U9") (pin "9") (pinfunction "~{DSR}_9") (pintype "input+no_connect"))
    )
    (net (code "78") (name "unconnected-(U9-~{DTR}-Pad2)") (class "Default")
      (node (ref "U9") (pin "2") (pinfunction "~{DTR}_2") (pintype "output+no_connect"))
    )
    (net (code "79") (name "unconnected-(U9-~{RI}-Pad6)") (class "Default")
      (node (ref "U9") (pin "6") (pinfunction "~{RI}_6") (pintype "input+no_connect"))
    )
    (net (code "80") (name "unconnected-(U9-~{RTS}-Pad3)") (class "Default")
      (node (ref "U9") (pin "3") (pinfunction "~{RTS}_3") (pintype "output+no_connect"))
    )
  )
)
